# adapter.net
KiCad netlist of a schematic drawn in EAGLE
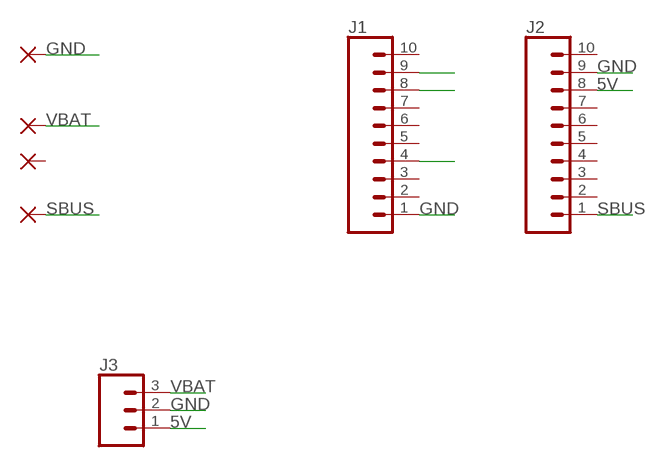
[diagram p0: schematic, sheet 1]

(export (version "E")
  (design (tool "Eeschema 10.0.6"))
  (components
    (comp (ref "GND")
      (value "SMD2")
      (footprint "eagle-import:SMD1,27-2,54")
      (libsource (lib "eagle-import") (part "SMD2"))
    )
    (comp (ref "J1")
      (value "CONN_10NO_SILK_PTH_FEMALE")
      (footprint "eagle-import:1X10_NO_SILK")
      (libsource (lib "eagle-import") (part "CONN_10NO_SILK_PTH_FEMALE"))
    )
    (comp (ref "J2")
      (value "CONN_10NO_SILK_PTH_FEMALE")
      (footprint "eagle-import:1X10_NO_SILK")
      (libsource (lib "eagle-import") (part "CONN_10NO_SILK_PTH_FEMALE"))
    )
    (comp (ref "J3")
      (value "CONN_031X03_NO_SILK")
      (footprint "eagle-import:1X03_NO_SILK")
      (libsource (lib "eagle-import") (part "CONN_031X03_NO_SILK"))
    )
    (comp (ref "PAD1")
      (value "SMD2")
      (footprint "eagle-import:SMD1,27-2,54")
      (libsource (lib "eagle-import") (part "SMD2"))
    )
    (comp (ref "SBUS")
      (value "SMD2")
      (footprint "eagle-import:SMD1,27-2,54")
      (libsource (lib "eagle-import") (part "SMD2"))
    )
    (comp (ref "VBAT")
      (value "SMD2")
      (footprint "eagle-import:SMD1,27-2,54")
      (libsource (lib "eagle-import") (part "SMD2"))
    )
  )
  (nets
    (net (code "1") (name "/5V") (class "Default")
      (node (ref "J2") (pin "8") (pinfunction "8_8") (pintype "passive"))
      (node (ref "J3") (pin "1") (pinfunction "1_1") (pintype "passive"))
    )
    (net (code "2") (name "/GND") (class "Default")
      (node (ref "GND") (pin "1") (pinfunction "P_1") (pintype "passive"))
      (node (ref "J1") (pin "1") (pinfunction "1_1") (pintype "passive"))
      (node (ref "J2") (pin "9") (pinfunction "9_9") (pintype "passive"))
      (node (ref "J3") (pin "2") (pinfunction "2_2") (pintype "passive"))
    )
    (net (code "3") (name "/SBUS") (class "Default")
      (node (ref "J2") (pin "1") (pinfunction "1_1") (pintype "passive"))
      (node (ref "SBUS") (pin "1") (pinfunction "P_1") (pintype "passive"))
    )
    (net (code "4") (name "/VBAT") (class "Default")
      (node (ref "J3") (pin "3") (pinfunction "3_3") (pintype "passive"))
      (node (ref "VBAT") (pin "1") (pinfunction "P_1") (pintype "passive"))
    )
    (net (code "5") (name "unconnected-(J1-Pad2)") (class "Default")
      (node (ref "J1") (pin "2") (pinfunction "2_2") (pintype "passive"))
    )
    (net (code "6") (name "unconnected-(J1-Pad3)") (class "Default")
      (node (ref "J1") (pin "3") (pinfunction "3_3") (pintype "passive"))
    )
    (net (code "7") (name "unconnected-(J1-Pad4)") (class "Default")
      (node (ref "J1") (pin "4") (pinfunction "4_4") (pintype "passive"))
    )
    (net (code "8") (name "unconnected-(J1-Pad5)") (class "Default")
      (node (ref "J1") (pin "5") (pinfunction "5_5") (pintype "passive"))
    )
    (net (code "9") (name "unconnected-(J1-Pad6)") (class "Default")
      (node (ref "J1") (pin "6") (pinfunction "6_6") (pintype "passive"))
    )
    (net (code "10") (name "unconnected-(J1-Pad7)") (class "Default")
      (node (ref "J1") (pin "7") (pinfunction "7_7") (pintype "passive"))
    )
    (net (code "11") (name "unconnected-(J1-Pad8)") (class "Default")
      (node (ref "J1") (pin "8") (pinfunction "8_8") (pintype "passive"))
    )
    (net (code "12") (name "unconnected-(J1-Pad9)") (class "Default")
      (node (ref "J1") (pin "9") (pinfunction "9_9") (pintype "passive"))
    )
    (net (code "13") (name "unconnected-(J1-Pad10)") (class "Default")
      (node (ref "J1") (pin "10") (pinfunction "10_10") (pintype "passive"))
    )
    (net (code "14") (name "unconnected-(J2-Pad2)") (class "Default")
      (node (ref "J2") (pin "2") (pinfunction "2_2") (pintype "passive"))
    )
    (net (code "15") (name "unconnected-(J2-Pad3)") (class "Default")
      (node (ref "J2") (pin "3") (pinfunction "3_3") (pintype "passive"))
    )
    (net (code "16") (name "unconnected-(J2-Pad4)") (class "Default")
      (node (ref "J2") (pin "4") (pinfunction "4_4") (pintype "passive"))
    )
    (net (code "17") (name "unconnected-(J2-Pad5)") (class "Default")
      (node (ref "J2") (pin "5") (pinfunction "5_5") (pintype "passive"))
    )
    (net (code "18") (name "unconnected-(J2-Pad6)") (class "Default")
      (node (ref "J2") (pin "6") (pinfunction "6_6") (pintype "passive"))
    )
    (net (code "19") (name "unconnected-(J2-Pad7)") (class "Default")
      (node (ref "J2") (pin "7") (pinfunction "7_7") (pintype "passive"))
    )
    (net (code "20") (name "unconnected-(J2-Pad10)") (class "Default")
      (node (ref "J2") (pin "10") (pinfunction "10_10") (pintype "passive"))
    )
    (net (code "21") (name "unconnected-(PAD1-P-Pad1)") (class "Default")
      (node (ref "PAD1") (pin "1") (pinfunction "P_1") (pintype "passive"))
    )
  )
)
